# PR9018.net
KiCad netlist of a schematic drawn in EAGLE
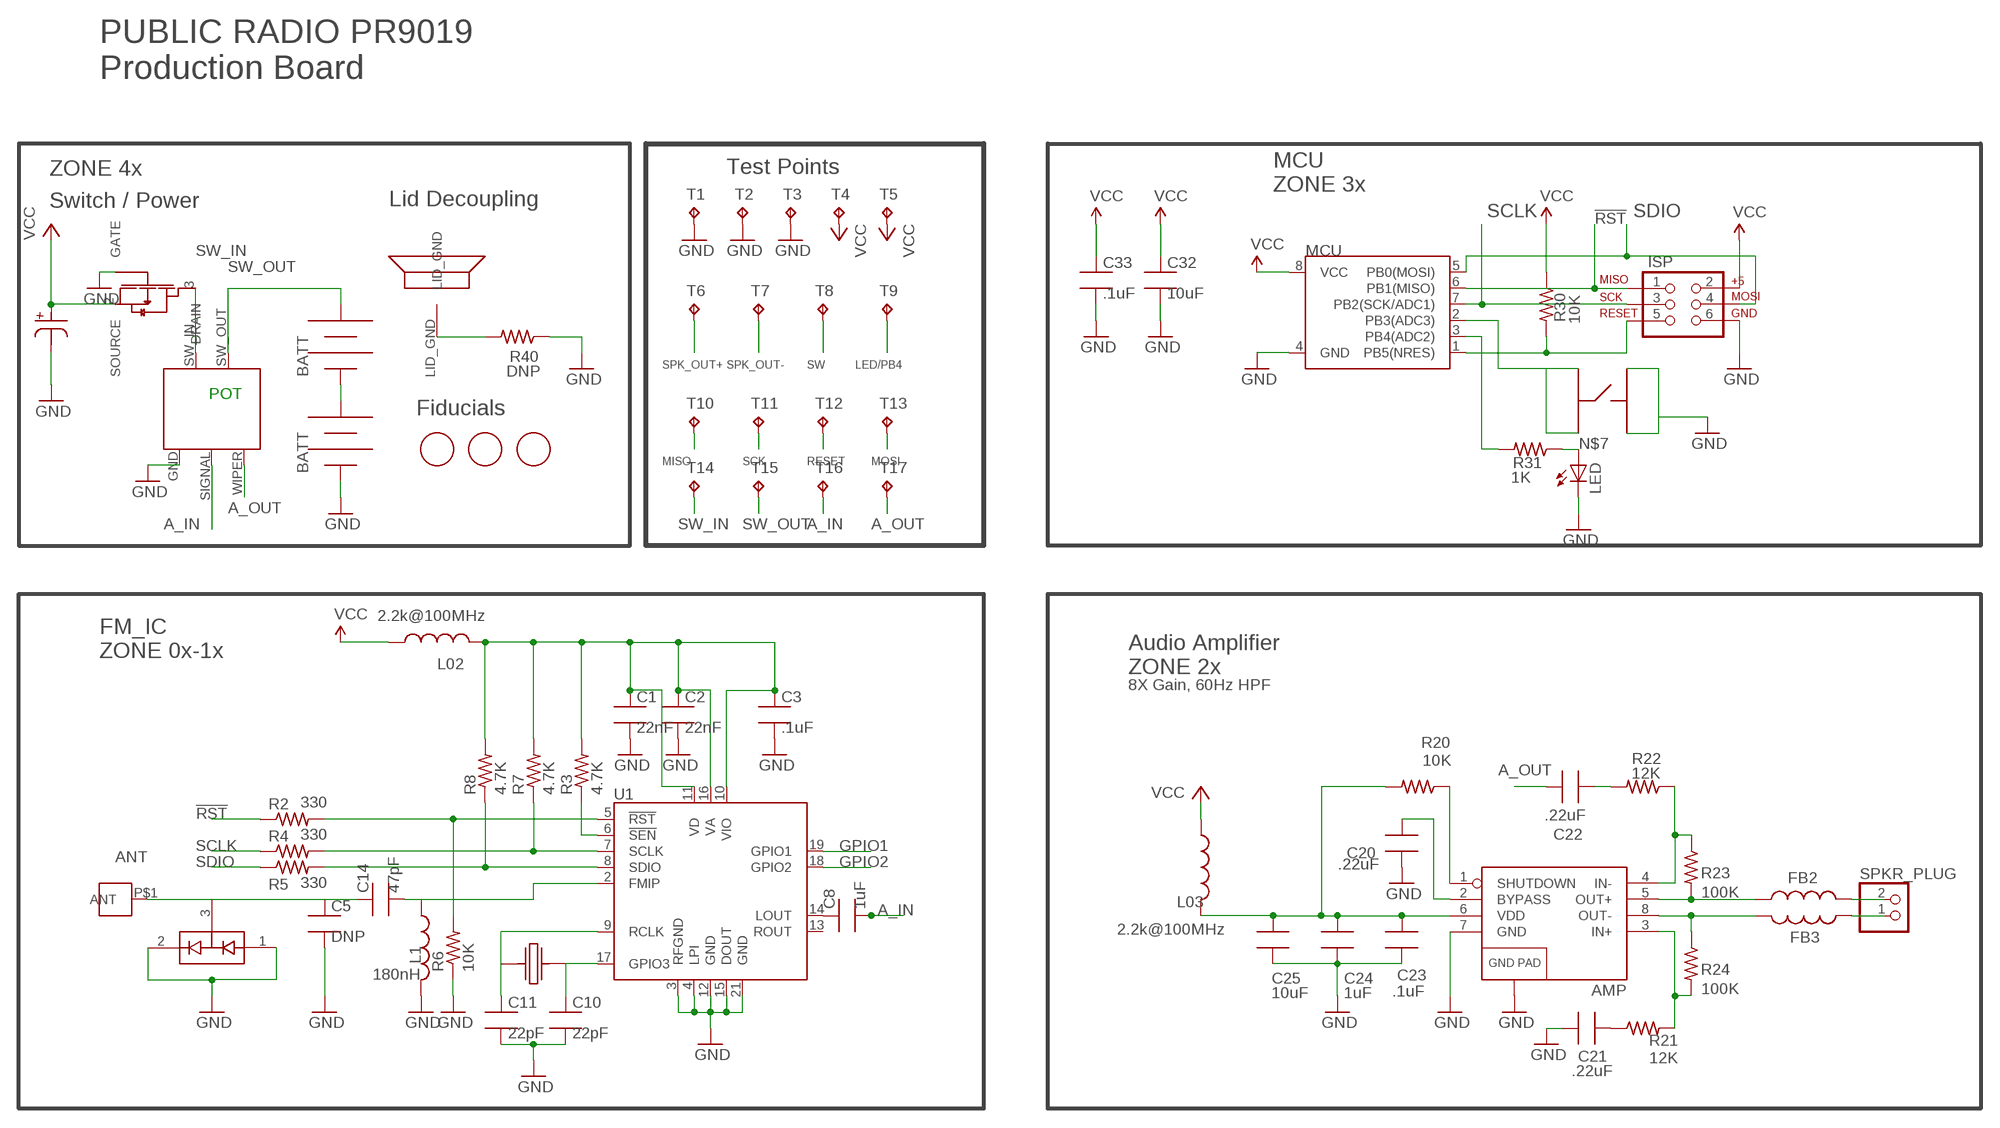
[diagram p0: schematic, sheet 1]

(export (version "E")
  (design (tool "Eeschema 10.0.6"))
  (components
    (comp (ref "AMP")
      (value "TPA6203A1")
      (footprint "eagle-import:8-MSOP")
      (libsource (lib "eagle-import") (part "TPA6203A1"))
    )
    (comp (ref "ANT_MOUNT")
      (value "DNP")
      (footprint "eagle-import:M3_BOLT_HOLE")
      (libsource (lib "eagle-import") (part "M3_SCREW_POST"))
    )
    (comp (ref "C1")
      (value "22nF")
      (footprint "eagle-import:0603_CPL")
      (fields
        (field (name "MFG_PN") "CL10B223KB8NNNC")
        (field (name "TOL") "10%")
        (field (name "VOLTAGE") "16V")
      )
      (libsource (lib "eagle-import") (part "C_SMT_0603_CPL"))
    )
    (comp (ref "C2")
      (value "22nF")
      (footprint "eagle-import:0603_CPL")
      (fields
        (field (name "MFG_PN") "CL10B223KB8NNNC")
        (field (name "TOL") "10%")
        (field (name "VOLTAGE") "16V")
      )
      (libsource (lib "eagle-import") (part "C_SMT_0603_CPL"))
    )
    (comp (ref "C3")
      (value ".1uF")
      (footprint "eagle-import:0603_CPL")
      (fields
        (field (name "MFG_PN") "CL10B104KB8SFNC")
        (field (name "TOL") "10%")
        (field (name "VOLTAGE") "16V")
      )
      (libsource (lib "eagle-import") (part "C_SMT_0603_CPL"))
    )
    (comp (ref "C5")
      (value "DNP")
      (footprint "eagle-import:0603_CPL")
      (fields (field (name "MFG_PN") "DNP") (field (name "TOL") "2%") (field (name "VOLTAGE") "50V"))
      (libsource (lib "eagle-import") (part "C_SMT_0603_CPL"))
    )
    (comp (ref "C8")
      (value "1uF")
      (footprint "eagle-import:0603_CPL")
      (fields
        (field (name "MFG_PN") "CL10B105KP8NNNC")
        (field (name "TOL") "10%")
        (field (name "VOLTAGE") "10V")
      )
      (libsource (lib "eagle-import") (part "C_SMT_0603_CPL"))
    )
    (comp (ref "C10")
      (value "22pF")
      (footprint "eagle-import:0603_CPL")
      (fields
        (field (name "MFG_PN") "C1608C0G1H220J080AA")
        (field (name "TOL") "5%")
        (field (name "VOLTAGE") "50V")
      )
      (libsource (lib "eagle-import") (part "C_SMT_0603_CPL"))
    )
    (comp (ref "C11")
      (value "22pF")
      (footprint "eagle-import:0603_CPL")
      (fields
        (field (name "MFG_PN") "C1608C0G1H220J080AA")
        (field (name "TOL") "5%")
        (field (name "VOLTAGE") "50V")
      )
      (libsource (lib "eagle-import") (part "C_SMT_0603_CPL"))
    )
    (comp (ref "C14")
      (value "47pF")
      (footprint "eagle-import:0603_CPL")
      (fields
        (field (name "MFG_PN") "CL10C470JB8NCNC")
        (field (name "TOL") "5%")
        (field (name "VOLTAGE") "50V")
      )
      (libsource (lib "eagle-import") (part "C_SMT_0603_CPL"))
    )
    (comp (ref "C20")
      (value ".22uF")
      (footprint "eagle-import:0603_CPL")
      (fields
        (field (name "MFG_PN") "C1608X7R1C224K080AC")
        (field (name "TOL") "10%")
        (field (name "VOLTAGE") "16V")
      )
      (libsource (lib "eagle-import") (part "C_SMT_0603_CPL"))
    )
    (comp (ref "C21")
      (value ".22uF")
      (footprint "eagle-import:0603_CPL")
      (fields
        (field (name "MFG_PN") "C1608X7R1C224K080AC")
        (field (name "TOL") "10%")
        (field (name "VOLTAGE") "16V")
      )
      (libsource (lib "eagle-import") (part "C_SMT_0603_CPL"))
    )
    (comp (ref "C22")
      (value ".22uF")
      (footprint "eagle-import:0603_CPL")
      (fields
        (field (name "MFG_PN") "C1608X7R1C224K080AC")
        (field (name "TOL") "10%")
        (field (name "VOLTAGE") "16V")
      )
      (libsource (lib "eagle-import") (part "C_SMT_0603_CPL"))
    )
    (comp (ref "C23")
      (value ".1uF")
      (footprint "eagle-import:0603_CPL")
      (fields
        (field (name "MFG_PN") "CL10B104KB8SFNC")
        (field (name "TOL") "10%")
        (field (name "VOLTAGE") "16V")
      )
      (libsource (lib "eagle-import") (part "C_SMT_0603_CPL"))
    )
    (comp (ref "C24")
      (value "1uF")
      (footprint "eagle-import:0603_CPL")
      (fields
        (field (name "MFG_PN") "CL10B105KP8NNNC")
        (field (name "TOL") "10%")
        (field (name "VOLTAGE") "10V")
      )
      (libsource (lib "eagle-import") (part "C_SMT_0603_CPL"))
    )
    (comp (ref "C25")
      (value "10uF")
      (footprint "eagle-import:0603_CPL")
      (fields
        (field (name "MFG_PN") "CL10A106MQ8NNNC")
        (field (name "TOL") "20%")
        (field (name "VOLTAGE") "6.3V")
      )
      (libsource (lib "eagle-import") (part "C_SMT_0603_CPL"))
    )
    (comp (ref "C32")
      (value "10uF")
      (footprint "eagle-import:0603_CPL")
      (fields
        (field (name "MFG_PN") "CL10A106MQ8NNNC")
        (field (name "TOL") "20%")
        (field (name "VOLTAGE") "6.3V")
      )
      (libsource (lib "eagle-import") (part "C_SMT_0603_CPL"))
    )
    (comp (ref "C33")
      (value ".1uF")
      (footprint "eagle-import:0603_CPL")
      (fields
        (field (name "MFG_PN") "CL10B104KB8SFNC")
        (field (name "TOL") "10%")
        (field (name "VOLTAGE") "16V")
      )
      (libsource (lib "eagle-import") (part "C_SMT_0603_CPL"))
    )
    (comp (ref "C40")
      (value "220uF")
      (footprint "eagle-import:NICHICON_UD_63")
      (fields (field (name "TOL") "20%") (field (name "VOLTAGE") "16V"))
      (libsource (lib "eagle-import") (part "NICHICON_SERIESUD"))
    )
    (comp (ref "D1")
      (value "BAV99")
      (footprint "eagle-import:SOT23_CPL")
      (fields (field (name "MFG_PN") "BAV99,215"))
      (libsource (lib "eagle-import") (part "BAV99"))
    )
    (comp (ref "FB2")
      (value "L_SMT_0805_ADAFRUIT")
      (footprint "eagle-import:0805_ADAFRUIT")
      (fields
        (field (name "CURRENT") "2A")
        (field (name "DCR") "45m")
        (field (name "MFG_PN") "HI0805R800R-10")
      )
      (libsource (lib "eagle-import") (part "L_SMT_0805_ADAFRUIT"))
    )
    (comp (ref "FB3")
      (value "L_SMT_0805_ADAFRUIT")
      (footprint "eagle-import:0805_ADAFRUIT")
      (fields
        (field (name "CURRENT") "2A")
        (field (name "DCR") "45m")
        (field (name "MFG_PN") "HI0805R800R-10")
      )
      (libsource (lib "eagle-import") (part "L_SMT_0805_ADAFRUIT"))
    )
    (comp (ref "FET1")
      (value "AO3435")
      (footprint "eagle-import:SOT23_CPL")
      (fields (field (name "MFG_PN") "AO3435"))
      (libsource (lib "eagle-import") (part "AO3435"))
    )
    (comp (ref "ISP")
      (value "AVR_SPI_PRG_6NS")
      (footprint "eagle-import:2X3-NS")
      (libsource (lib "eagle-import") (part "AVR_SPI_PRG_6NS"))
    )
    (comp (ref "JP5")
      (value "BK-92_MPD_AA_BATT_CLIP")
      (footprint "eagle-import:BK92_AA_BATT")
      (fields (field (name "MFG_PN") "2 of BK92 - supplied by CL Labs"))
      (libsource (lib "eagle-import") (part "BK-92_MPD_AA_BATT_CLIP"))
    )
    (comp (ref "JP6")
      (value "BK-92_MPD_AA_BATT_CLIP")
      (footprint "eagle-import:BK92_AA_BATT")
      (fields (field (name "MFG_PN") "2 of BK92 - supplied by CL Labs"))
      (libsource (lib "eagle-import") (part "BK-92_MPD_AA_BATT_CLIP"))
    )
    (comp (ref "L1")
      (value "180nH")
      (footprint "eagle-import:0805_ADAFRUIT")
      (fields
        (field (name "CURRENT") "400mA")
        (field (name "DCR") "640m")
        (field (name "MFG_PN") "AISC-0805-R18J-T")
        (field (name "TOL") "5%")
      )
      (libsource (lib "eagle-import") (part "L_SMT_0805_ADAFRUIT"))
    )
    (comp (ref "L02")
      (value "2.2k@100MHz")
      (footprint "eagle-import:0603_CPL")
      (fields
        (field (name "CURRENT") "150mA")
        (field (name "DCR") "2.3")
        (field (name "MFG_PN") "HZ0603A222R-10")
      )
      (libsource (lib "eagle-import") (part "L_SMT_0603_CPL"))
    )
    (comp (ref "L03")
      (value "2.2k@100MHz")
      (footprint "eagle-import:0603_CPL")
      (fields
        (field (name "CURRENT") "150mA")
        (field (name "DCR") "2.3")
        (field (name "MFG_PN") "HZ0603A222R-10")
      )
      (libsource (lib "eagle-import") (part "L_SMT_0603_CPL"))
    )
    (comp (ref "LED")
      (value "LED")
      (footprint "eagle-import:0603_CPL")
      (fields (field (name "MFG_PN") "LY R976-PS-36"))
      (libsource (lib "eagle-import") (part "LED"))
    )
    (comp (ref "MARK1")
      (value "FIDUCIAL")
      (footprint "eagle-import:FIDUCIAL_1MM")
      (libsource (lib "eagle-import") (part "FIDUCIAL"))
    )
    (comp (ref "MARK2")
      (value "FIDUCIAL")
      (footprint "eagle-import:FIDUCIAL_1MM")
      (libsource (lib "eagle-import") (part "FIDUCIAL"))
    )
    (comp (ref "MARK3")
      (value "FIDUCIAL")
      (footprint "eagle-import:FIDUCIAL_1MM")
      (libsource (lib "eagle-import") (part "FIDUCIAL"))
    )
    (comp (ref "MCU")
      (value "ATTINY45TINY45-20-SMT")
      (footprint "eagle-import:8-SOIC")
      (libsource (lib "eagle-import") (part "ATTINY45TINY45-20-SMT"))
    )
    (comp (ref "R1")
      (value "RV170SF_TAIWANA_POT_SW")
      (footprint "eagle-import:RV170SF_SW_POT")
      (fields (field (name "MFG_PN") "RV170SF-43-20F-A10K - supplied by CL Labs"))
      (libsource (lib "eagle-import") (part "RV170SF_TAIWANA_POT_SW"))
    )
    (comp (ref "R2")
      (value "330")
      (footprint "eagle-import:0603_CPL")
      (fields (field (name "MFG_PN") "MCR03ERTJ331") (field (name "POWER") "1/10W") (field (name "TOL") "5%"))
      (libsource (lib "eagle-import") (part "R_SMT_R0603_CPL"))
    )
    (comp (ref "R3")
      (value "4.7K")
      (footprint "eagle-import:0603_CPL")
      (fields
        (field (name "MFG_PN") "ERJ-3EKF4701V")
        (field (name "POWER") "1/10W")
        (field (name "TOL") "1%")
      )
      (libsource (lib "eagle-import") (part "R_SMT_R0603_CPL"))
    )
    (comp (ref "R4")
      (value "330")
      (footprint "eagle-import:0603_CPL")
      (fields (field (name "MFG_PN") "MCR03ERTJ331") (field (name "POWER") "1/10W") (field (name "TOL") "5%"))
      (libsource (lib "eagle-import") (part "R_SMT_R0603_CPL"))
    )
    (comp (ref "R5")
      (value "330")
      (footprint "eagle-import:0603_CPL")
      (fields (field (name "MFG_PN") "MCR03ERTJ331") (field (name "POWER") "1/10W") (field (name "TOL") "5%"))
      (libsource (lib "eagle-import") (part "R_SMT_R0603_CPL"))
    )
    (comp (ref "R6")
      (value "10K")
      (footprint "eagle-import:0603_CPL")
      (fields
        (field (name "MFG_PN") "ERJ-3GEYJ103V")
        (field (name "POWER") "1/10W")
        (field (name "TOL") "5%")
      )
      (libsource (lib "eagle-import") (part "R_SMT_R0603_CPL"))
    )
    (comp (ref "R7")
      (value "4.7K")
      (footprint "eagle-import:0603_CPL")
      (fields
        (field (name "MFG_PN") "ERJ-3EKF4701V")
        (field (name "POWER") "1/10W")
        (field (name "TOL") "1%")
      )
      (libsource (lib "eagle-import") (part "R_SMT_R0603_CPL"))
    )
    (comp (ref "R8")
      (value "4.7K")
      (footprint "eagle-import:0603_CPL")
      (fields
        (field (name "MFG_PN") "ERJ-3EKF4701V")
        (field (name "POWER") "1/10W")
        (field (name "TOL") "1%")
      )
      (libsource (lib "eagle-import") (part "R_SMT_R0603_CPL"))
    )
    (comp (ref "R20")
      (value "10K")
      (footprint "eagle-import:0603_CPL")
      (fields
        (field (name "MFG_PN") "ERJ-3GEYJ103V")
        (field (name "POWER") "1/10W")
        (field (name "TOL") "5%")
      )
      (libsource (lib "eagle-import") (part "R_SMT_R0603_CPL"))
    )
    (comp (ref "R21")
      (value "12K")
      (footprint "eagle-import:0603_CPL")
      (fields
        (field (name "MFG_PN") "RC0603FR-0712KL")
        (field (name "POWER") "1/10W")
        (field (name "TOL") "1%")
      )
      (libsource (lib "eagle-import") (part "R_SMT_R0603_CPL"))
    )
    (comp (ref "R22")
      (value "12K")
      (footprint "eagle-import:0603_CPL")
      (fields
        (field (name "MFG_PN") "RC0603FR-0712KL")
        (field (name "POWER") "1/10W")
        (field (name "TOL") "1%")
      )
      (libsource (lib "eagle-import") (part "R_SMT_R0603_CPL"))
    )
    (comp (ref "R23")
      (value "100K")
      (footprint "eagle-import:0603_CPL")
      (fields
        (field (name "MFG_PN") "ERJ-3EKF1003V")
        (field (name "POWER") "1/10W")
        (field (name "TOL") "1%")
      )
      (libsource (lib "eagle-import") (part "R_SMT_R0603_CPL"))
    )
    (comp (ref "R24")
      (value "100K")
      (footprint "eagle-import:0603_CPL")
      (fields
        (field (name "MFG_PN") "ERJ-3EKF1003V")
        (field (name "POWER") "1/10W")
        (field (name "TOL") "1%")
      )
      (libsource (lib "eagle-import") (part "R_SMT_R0603_CPL"))
    )
    (comp (ref "R30")
      (value "10K")
      (footprint "eagle-import:0603_CPL")
      (fields
        (field (name "MFG_PN") "ERJ-3GEYJ103V")
        (field (name "POWER") "1/10W")
        (field (name "TOL") "5%")
      )
      (libsource (lib "eagle-import") (part "R_SMT_R0603_CPL"))
    )
    (comp (ref "R31")
      (value "1K")
      (footprint "eagle-import:0603_CPL")
      (fields
        (field (name "MFG_PN") "ERJ-3EKF1001V")
        (field (name "POWER") "1/10W")
        (field (name "TOL") "1%")
      )
      (libsource (lib "eagle-import") (part "R_SMT_R0603_CPL"))
    )
    (comp (ref "R40")
      (value "DNP")
      (footprint "eagle-import:0603_CPL")
      (fields (field (name "MFG_PN") "ERJ-3GEY0R00V"))
      (libsource (lib "eagle-import") (part "R_SMT_R0603_CPL"))
    )
    (comp (ref "SPKR_PLACE")
      (value "DNP")
      (footprint "eagle-import:PR2023_SPKR_PLACE")
      (libsource (lib "eagle-import") (part "PR2023_SPKR"))
    )
    (comp (ref "SPKR_PLUG")
      (value "JST_2PIN-SMT-RA")
      (footprint "eagle-import:JST-B2B-PH-SM4-TB")
      (libsource (lib "eagle-import") (part "JST_2PIN-SMT-RA"))
    )
    (comp (ref "SW1")
      (value "C&K_PTS645")
      (footprint "eagle-import:C&K_PTS645_SMT")
      (libsource (lib "eagle-import") (part "C&K_PTS645"))
    )
    (comp (ref "T1")
      (value "TPTP20R")
      (footprint "eagle-import:TP20R")
      (libsource (lib "eagle-import") (part "TPTP20R"))
    )
    (comp (ref "T2")
      (value "TPTP20R")
      (footprint "eagle-import:TP20R")
      (libsource (lib "eagle-import") (part "TPTP20R"))
    )
    (comp (ref "T3")
      (value "TPTP20R")
      (footprint "eagle-import:TP20R")
      (libsource (lib "eagle-import") (part "TPTP20R"))
    )
    (comp (ref "T4")
      (value "TPTP20R")
      (footprint "eagle-import:TP20R")
      (libsource (lib "eagle-import") (part "TPTP20R"))
    )
    (comp (ref "T5")
      (value "TPTP20R")
      (footprint "eagle-import:TP20R")
      (libsource (lib "eagle-import") (part "TPTP20R"))
    )
    (comp (ref "T6")
      (value "TPTP20R")
      (footprint "eagle-import:TP20R")
      (libsource (lib "eagle-import") (part "TPTP20R"))
    )
    (comp (ref "T7")
      (value "TPTP20R")
      (footprint "eagle-import:TP20R")
      (libsource (lib "eagle-import") (part "TPTP20R"))
    )
    (comp (ref "T8")
      (value "TPTP20R")
      (footprint "eagle-import:TP20R")
      (libsource (lib "eagle-import") (part "TPTP20R"))
    )
    (comp (ref "T9")
      (value "TPTP20R")
      (footprint "eagle-import:TP20R")
      (libsource (lib "eagle-import") (part "TPTP20R"))
    )
    (comp (ref "T10")
      (value "TPTP20R")
      (footprint "eagle-import:TP20R")
      (libsource (lib "eagle-import") (part "TPTP20R"))
    )
    (comp (ref "T11")
      (value "TPTP20R")
      (footprint "eagle-import:TP20R")
      (libsource (lib "eagle-import") (part "TPTP20R"))
    )
    (comp (ref "T12")
      (value "TPTP20R")
      (footprint "eagle-import:TP20R")
      (libsource (lib "eagle-import") (part "TPTP20R"))
    )
    (comp (ref "T13")
      (value "TPTP20R")
      (footprint "eagle-import:TP20R")
      (libsource (lib "eagle-import") (part "TPTP20R"))
    )
    (comp (ref "T14")
      (value "TPTP20R")
      (footprint "eagle-import:TP20R")
      (libsource (lib "eagle-import") (part "TPTP20R"))
    )
    (comp (ref "T15")
      (value "TPTP20R")
      (footprint "eagle-import:TP20R")
      (libsource (lib "eagle-import") (part "TPTP20R"))
    )
    (comp (ref "T16")
      (value "TPTP20R")
      (footprint "eagle-import:TP20R")
      (libsource (lib "eagle-import") (part "TPTP20R"))
    )
    (comp (ref "T17")
      (value "TPTP20R")
      (footprint "eagle-import:TP20R")
      (libsource (lib "eagle-import") (part "TPTP20R"))
    )
    (comp (ref "U1")
      (value "SI4702-C19-GMR")
      (footprint "eagle-import:SI470X_20_QFN")
      (fields (field (name "MFG_PN") "Si4702 C19 GM - supplied by CL Labs"))
      (libsource (lib "eagle-import") (part "SI4702-C19-GMR"))
    )
    (comp (ref "X1")
      (value "ABS25XTAL")
      (footprint "eagle-import:4-SOJ")
      (libsource (lib "eagle-import") (part "ABS25XTAL"))
    )
  )
  (nets
    (net (code "1") (name "/ANT") (class "Default")
      (node (ref "ANT_MOUNT") (pin "P$1") (pinfunction "ANT_P$1") (pintype "bidirectional"))
      (node (ref "C14") (pin "1") (pinfunction "1_1") (pintype "passive"))
      (node (ref "C5") (pin "1") (pinfunction "1_1") (pintype "passive"))
      (node (ref "D1") (pin "3") (pinfunction "COM_3") (pintype "bidirectional"))
    )
    (net (code "2") (name "/A_IN") (class "Default")
      (node (ref "C8") (pin "2") (pinfunction "2_2") (pintype "passive"))
      (node (ref "R1") (pin "SIGNAL") (pinfunction "SIGNAL_SIGNAL") (pintype "bidirectional"))
      (node (ref "T16") (pin "TP") (pinfunction "TP_TP") (pintype "input"))
    )
    (net (code "3") (name "/A_OUT") (class "Default")
      (node (ref "C22") (pin "2") (pinfunction "2_2") (pintype "passive"))
      (node (ref "R1") (pin "WIPER") (pinfunction "WIPER_WIPER") (pintype "bidirectional"))
      (node (ref "T17") (pin "TP") (pinfunction "TP_TP") (pintype "input"))
    )
    (net (code "4") (name "/GPIO1") (class "Default")
      (node (ref "U1") (pin "19") (pinfunction "GPIO1_19") (pintype "bidirectional"))
    )
    (net (code "5") (name "/GPIO2") (class "Default")
      (node (ref "U1") (pin "18") (pinfunction "GPIO2_18") (pintype "bidirectional"))
    )
    (net (code "6") (name "/LED{slash}PB4") (class "Default")
      (node (ref "MCU") (pin "3") (pinfunction "PB4(ADC2)_3") (pintype "bidirectional"))
      (node (ref "R31") (pin "2") (pinfunction "2_2") (pintype "passive"))
      (node (ref "T9") (pin "TP") (pinfunction "TP_TP") (pintype "input"))
    )
    (net (code "7") (name "/N$7") (class "Default")
      (node (ref "LED") (pin "1") (pinfunction "A_1") (pintype "passive"))
      (node (ref "R31") (pin "1") (pinfunction "1_1") (pintype "passive"))
    )
    (net (code "8") (name "/RESET") (class "Default")
      (node (ref "ISP") (pin "5") (pinfunction "5_5") (pintype "passive"))
      (node (ref "MCU") (pin "1") (pinfunction "PB5(NRES)_1") (pintype "bidirectional"))
      (node (ref "R30") (pin "2") (pinfunction "2_2") (pintype "passive"))
      (node (ref "T12") (pin "TP") (pinfunction "TP_TP") (pintype "input"))
    )
    (net (code "9") (name "/SCLK") (class "Default")
      (node (ref "ISP") (pin "3") (pinfunction "3_3") (pintype "passive"))
      (node (ref "MCU") (pin "7") (pinfunction "PB2(SCK/ADC1)_7") (pintype "bidirectional"))
      (node (ref "R4") (pin "1") (pinfunction "1_1") (pintype "passive"))
      (node (ref "T11") (pin "TP") (pinfunction "TP_TP") (pintype "input"))
    )
    (net (code "10") (name "/SDIO") (class "Default")
      (node (ref "ISP") (pin "4") (pinfunction "4_4") (pintype "passive"))
      (node (ref "MCU") (pin "5") (pinfunction "PB0(MOSI)_5") (pintype "bidirectional"))
      (node (ref "R5") (pin "1") (pinfunction "1_1") (pintype "passive"))
      (node (ref "T13") (pin "TP") (pinfunction "TP_TP") (pintype "input"))
    )
    (net (code "11") (name "/SPK_OUT+") (class "Default")
      (node (ref "FB2") (pin "2") (pinfunction "2_2") (pintype "passive"))
      (node (ref "SPKR_PLUG") (pin "2") (pinfunction "1_2") (pintype "passive"))
      (node (ref "T6") (pin "TP") (pinfunction "TP_TP") (pintype "input"))
    )
    (net (code "12") (name "/SPK_OUT-") (class "Default")
      (node (ref "FB3") (pin "1") (pinfunction "1_1") (pintype "passive"))
      (node (ref "SPKR_PLUG") (pin "1") (pinfunction "2_1") (pintype "passive"))
      (node (ref "T7") (pin "TP") (pinfunction "TP_TP") (pintype "input"))
    )
    (net (code "13") (name "/SW") (class "Default")
      (node (ref "MCU") (pin "2") (pinfunction "PB3(ADC3)_2") (pintype "bidirectional"))
      (node (ref "SW1") (pin "P$3") (pinfunction "P$3_P$3") (pintype "bidirectional"))
      (node (ref "SW1") (pin "P$4") (pinfunction "P$4_P$4") (pintype "bidirectional"))
      (node (ref "T8") (pin "TP") (pinfunction "TP_TP") (pintype "input"))
    )
    (net (code "14") (name "/SW_IN") (class "Default")
      (node (ref "FET1") (pin "3") (pinfunction "DRAIN_3") (pintype "bidirectional"))
      (node (ref "R1") (pin "SW_IN") (pinfunction "SW_IN_SW_IN") (pintype "bidirectional"))
      (node (ref "T14") (pin "TP") (pinfunction "TP_TP") (pintype "input"))
    )
    (net (code "15") (name "/SW_OUT") (class "Default")
      (node (ref "JP5") (pin "POS") (pinfunction "POS_POS") (pintype "bidirectional"))
      (node (ref "JP5") (pin "POS@2") (pinfunction "POS_POS@2") (pintype "bidirectional"))
      (node (ref "R1") (pin "SW_OUT") (pinfunction "SW_OUT_SW_OUT") (pintype "bidirectional"))
      (node (ref "T15") (pin "TP") (pinfunction "TP_TP") (pintype "input"))
    )
    (net (code "16") (name "/~{RST}") (class "Default")
      (node (ref "ISP") (pin "1") (pinfunction "1_1") (pintype "passive"))
      (node (ref "MCU") (pin "6") (pinfunction "PB1(MISO)_6") (pintype "bidirectional"))
      (node (ref "R2") (pin "1") (pinfunction "1_1") (pintype "passive"))
      (node (ref "T10") (pin "TP") (pinfunction "TP_TP") (pintype "input"))
    )
    (net (code "17") (name "GND") (class "Default")
      (node (ref "AMP") (pin "7") (pinfunction "GND_7") (pintype "power_in"))
      (node (ref "AMP") (pin "9") (pinfunction "GND_9") (pintype "power_in"))
      (node (ref "C1") (pin "2") (pinfunction "2_2") (pintype "passive"))
      (node (ref "C10") (pin "2") (pinfunction "2_2") (pintype "passive"))
      (node (ref "C11") (pin "2") (pinfunction "2_2") (pintype "passive"))
      (node (ref "C2") (pin "2") (pinfunction "2_2") (pintype "passive"))
      (node (ref "C20") (pin "1") (pinfunction "1_1") (pintype "passive"))
      (node (ref "C21") (pin "1") (pinfunction "1_1") (pintype "passive"))
      (node (ref "C23") (pin "2") (pinfunction "2_2") (pintype "passive"))
      (node (ref "C24") (pin "2") (pinfunction "2_2") (pintype "passive"))
      (node (ref "C25") (pin "2") (pinfunction "2_2") (pintype "passive"))
      (node (ref "C3") (pin "2") (pinfunction "2_2") (pintype "passive"))
      (node (ref "C32") (pin "2") (pinfunction "2_2") (pintype "passive"))
      (node (ref "C33") (pin "2") (pinfunction "2_2") (pintype "passive"))
      (node (ref "C40") (pin "P$2") (pinfunction "P$2_P$2") (pintype "bidirectional"))
      (node (ref "C5") (pin "2") (pinfunction "2_2") (pintype "passive"))
      (node (ref "D1") (pin "1") (pinfunction "A1_1") (pintype "bidirectional"))
      (node (ref "D1") (pin "2") (pinfunction "C2_2") (pintype "bidirectional"))
      (node (ref "FET1") (pin "1") (pinfunction "GATE_1") (pintype "bidirectional"))
      (node (ref "ISP") (pin "6") (pinfunction "6_6") (pintype "passive"))
      (node (ref "JP6") (pin "NEG") (pinfunction "NEG_NEG") (pintype "bidirectional"))
      (node (ref "JP6") (pin "NEG@2") (pinfunction "NEG_NEG@2") (pintype "bidirectional"))
      (node (ref "L1") (pin "2") (pinfunction "2_2") (pintype "passive"))
      (node (ref "LED") (pin "2") (pinfunction "C_2") (pintype "passive"))
      (node (ref "MCU") (pin "4") (pinfunction "GND_4") (pintype "bidirectional"))
      (node (ref "R1") (pin "GND") (pinfunction "GND_GND") (pintype "bidirectional"))
      (node (ref "R40") (pin "1") (pinfunction "1_1") (pintype "passive"))
      (node (ref "R6") (pin "1") (pinfunction "1_1") (pintype "passive"))
      (node (ref "SW1") (pin "P$1") (pinfunction "P$1_P$1") (pintype "bidirectional"))
      (node (ref "SW1") (pin "P$2") (pinfunction "P$2_P$2") (pintype "bidirectional"))
      (node (ref "T1") (pin "TP") (pinfunction "TP_TP") (pintype "input"))
      (node (ref "T2") (pin "TP") (pinfunction "TP_TP") (pintype "input"))
      (node (ref "T3") (pin "TP") (pinfunction "TP_TP") (pintype "input"))
      (node (ref "U1") (pin "12") (pinfunction "GND_12") (pintype "bidirectional"))
      (node (ref "U1") (pin "15") (pinfunction "DOUT_15") (pintype "bidirectional"))
      (node (ref "U1") (pin "21") (pinfunction "GND_21") (pintype "bidirectional"))
      (node (ref "U1") (pin "3") (pinfunction "RFGND_3") (pintype "bidirectional"))
      (node (ref "U1") (pin "4") (pinfunction "LPI_4") (pintype "bidirectional"))
    )
    (net (code "18") (name "Net-(AMP-BYPASS)") (class "Default")
      (node (ref "AMP") (pin "2") (pinfunction "BYPASS_2") (pintype "bidirectional"))
      (node (ref "C20") (pin "2") (pinfunction "2_2") (pintype "passive"))
    )
    (net (code "19") (name "Net-(AMP-IN+)") (class "Default")
      (node (ref "AMP") (pin "3") (pinfunction "IN+_3") (pintype "bidirectional"))
      (node (ref "R21") (pin "2") (pinfunction "2_2") (pintype "passive"))
      (node (ref "R24") (pin "2") (pinfunction "2_2") (pintype "passive"))
    )
    (net (code "20") (name "Net-(AMP-IN-)") (class "Default")
      (node (ref "AMP") (pin "4") (pinfunction "IN-_4") (pintype "bidirectional"))
      (node (ref "R22") (pin "1") (pinfunction "1_1") (pintype "passive"))
      (node (ref "R23") (pin "1") (pinfunction "1_1") (pintype "passive"))
    )
    (net (code "21") (name "Net-(AMP-OUT+)") (class "Default")
      (node (ref "AMP") (pin "5") (pinfunction "OUT+_5") (pintype "bidirectional"))
      (node (ref "FB2") (pin "1") (pinfunction "1_1") (pintype "passive"))
      (node (ref "R23") (pin "2") (pinfunction "2_2") (pintype "passive"))
    )
    (net (code "22") (name "Net-(AMP-OUT-)") (class "Default")
      (node (ref "AMP") (pin "8") (pinfunction "OUT-_8") (pintype "bidirectional"))
      (node (ref "FB3") (pin "2") (pinfunction "2_2") (pintype "passive"))
      (node (ref "R24") (pin "1") (pinfunction "1_1") (pintype "passive"))
    )
    (net (code "23") (name "Net-(AMP-SHUTDOWN)") (class "Default")
      (node (ref "AMP") (pin "1") (pinfunction "SHUTDOWN_1") (pintype "input"))
      (node (ref "R20") (pin "1") (pinfunction "1_1") (pintype "passive"))
    )
    (net (code "24") (name "Net-(AMP-VDD)") (class "Default")
      (node (ref "AMP") (pin "6") (pinfunction "VDD_6") (pintype "power_in"))
      (node (ref "C23") (pin "1") (pinfunction "1_1") (pintype "passive"))
      (node (ref "C24") (pin "1") (pinfunction "1_1") (pintype "passive"))
      (node (ref "C25") (pin "1") (pinfunction "1_1") (pintype "passive"))
      (node (ref "L03") (pin "2") (pinfunction "2_2") (pintype "passive"))
      (node (ref "R20") (pin "2") (pinfunction "2_2") (pintype "passive"))
    )
    (net (code "25") (name "Net-(C21-Pad2)") (class "Default")
      (node (ref "C21") (pin "2") (pinfunction "2_2") (pintype "passive"))
      (node (ref "R21") (pin "1") (pinfunction "1_1") (pintype "passive"))
    )
    (net (code "26") (name "Net-(C22-Pad1)") (class "Default")
      (node (ref "C22") (pin "1") (pinfunction "1_1") (pintype "passive"))
      (node (ref "R22") (pin "2") (pinfunction "2_2") (pintype "passive"))
    )
    (net (code "27") (name "Net-(JP5-NEG-PadNEG@2)") (class "Default")
      (node (ref "JP5") (pin "NEG") (pinfunction "NEG_NEG") (pintype "bidirectional"))
      (node (ref "JP5") (pin "NEG@2") (pinfunction "NEG_NEG@2") (pintype "bidirectional"))
      (node (ref "JP6") (pin "POS") (pinfunction "POS_POS") (pintype "bidirectional"))
      (node (ref "JP6") (pin "POS@2") (pinfunction "POS_POS@2") (pintype "bidirectional"))
    )
    (net (code "28") (name "Net-(R40-Pad2)") (class "Default")
      (node (ref "R40") (pin "2") (pinfunction "2_2") (pintype "passive"))
      (node (ref "SPKR_PLACE") (pin "LID_GND") (pinfunction "LID_GND_LID_GND") (pintype "bidirectional"))
    )
    (net (code "29") (name "Net-(U1-FMIP)") (class "Default")
      (node (ref "C14") (pin "2") (pinfunction "2_2") (pintype "passive"))
      (node (ref "L1") (pin "1") (pinfunction "1_1") (pintype "passive"))
      (node (ref "U1") (pin "2") (pinfunction "FMIP_2") (pintype "bidirectional"))
    )
    (net (code "30") (name "Net-(U1-GPIO3)") (class "Default")
      (node (ref "C10") (pin "1") (pinfunction "1_1") (pintype "passive"))
      (node (ref "U1") (pin "17") (pinfunction "GPIO3_17") (pintype "bidirectional"))
      (node (ref "X1") (pin "P$4") (pinfunction "P$4_P$4") (pintype "bidirectional"))
    )
    (net (code "31") (name "Net-(U1-LOUT)") (class "Default")
      (node (ref "C8") (pin "1") (pinfunction "1_1") (pintype "passive"))
      (node (ref "U1") (pin "14") (pinfunction "LOUT_14") (pintype "bidirectional"))
    )
    (net (code "32") (name "Net-(U1-RCLK)") (class "Default")
      (node (ref "C11") (pin "1") (pinfunction "1_1") (pintype "passive"))
      (node (ref "U1") (pin "9") (pinfunction "RCLK_9") (pintype "bidirectional"))
      (node (ref "X1") (pin "P$1") (pinfunction "P$1_P$1") (pintype "bidirectional"))
    )
    (net (code "33") (name "Net-(U1-SCLK)") (class "Default")
      (node (ref "R4") (pin "2") (pinfunction "2_2") (pintype "passive"))
      (node (ref "R7") (pin "1") (pinfunction "1_1") (pintype "passive"))
      (node (ref "U1") (pin "7") (pinfunction "SCLK_7") (pintype "bidirectional"))
    )
    (net (code "34") (name "Net-(U1-SDIO)") (class "Default")
      (node (ref "R5") (pin "2") (pinfunction "2_2") (pintype "passive"))
      (node (ref "R8") (pin "1") (pinfunction "1_1") (pintype "passive"))
      (node (ref "U1") (pin "8") (pinfunction "SDIO_8") (pintype "bidirectional"))
    )
    (net (code "35") (name "Net-(U1-VA)") (class "Default")
      (node (ref "C1") (pin "1") (pinfunction "1_1") (pintype "passive"))
      (node (ref "C2") (pin "1") (pinfunction "1_1") (pintype "passive"))
      (node (ref "C3") (pin "1") (pinfunction "1_1") (pintype "passive"))
      (node (ref "L02") (pin "2") (pinfunction "2_2") (pintype "passive"))
      (node (ref "R3") (pin "2") (pinfunction "2_2") (pintype "passive"))
      (node (ref "R7") (pin "2") (pinfunction "2_2") (pintype "passive"))
      (node (ref "R8") (pin "2") (pinfunction "2_2") (pintype "passive"))
      (node (ref "U1") (pin "10") (pinfunction "VIO_10") (pintype "bidirectional"))
      (node (ref "U1") (pin "11") (pinfunction "VD_11") (pintype "bidirectional"))
      (node (ref "U1") (pin "16") (pinfunction "VA_16") (pintype "bidirectional"))
    )
    (net (code "36") (name "Net-(U1-~{RST})") (class "Default")
      (node (ref "R2") (pin "2") (pinfunction "2_2") (pintype "passive"))
      (node (ref "R6") (pin "2") (pinfunction "2_2") (pintype "passive"))
      (node (ref "U1") (pin "5") (pinfunction "~{RST}_5") (pintype "bidirectional"))
    )
    (net (code "37") (name "Net-(U1-~{SEN})") (class "Default")
      (node (ref "R3") (pin "1") (pinfunction "1_1") (pintype "passive"))
      (node (ref "U1") (pin "6") (pinfunction "~{SEN}_6") (pintype "bidirectional"))
    )
    (net (code "38") (name "VCC") (class "Default")
      (node (ref "C32") (pin "1") (pinfunction "1_1") (pintype "passive"))
      (node (ref "C33") (pin "1") (pinfunction "1_1") (pintype "passive"))
      (node (ref "C40") (pin "P$1") (pinfunction "P$1_P$1") (pintype "bidirectional"))
      (node (ref "FET1") (pin "2") (pinfunction "SOURCE_2") (pintype "bidirectional"))
      (node (ref "ISP") (pin "2") (pinfunction "2_2") (pintype "passive"))
      (node (ref "L02") (pin "1") (pinfunction "1_1") (pintype "passive"))
      (node (ref "L03") (pin "1") (pinfunction "1_1") (pintype "passive"))
      (node (ref "MCU") (pin "8") (pinfunction "VCC_8") (pintype "bidirectional"))
      (node (ref "R30") (pin "1") (pinfunction "1_1") (pintype "passive"))
      (node (ref "T4") (pin "TP") (pinfunction "TP_TP") (pintype "input"))
      (node (ref "T5") (pin "TP") (pinfunction "TP_TP") (pintype "input"))
    )
    (net (code "39") (name "unconnected-(U1-ROUT-Pad13)") (class "Default")
      (node (ref "U1") (pin "13") (pinfunction "ROUT_13") (pintype "bidirectional"))
    )
  )
)
